# MergenElektronik_DesignBlocks_USB_Type-C.net
KiCad netlist of a schematic drawn in Altium Designer
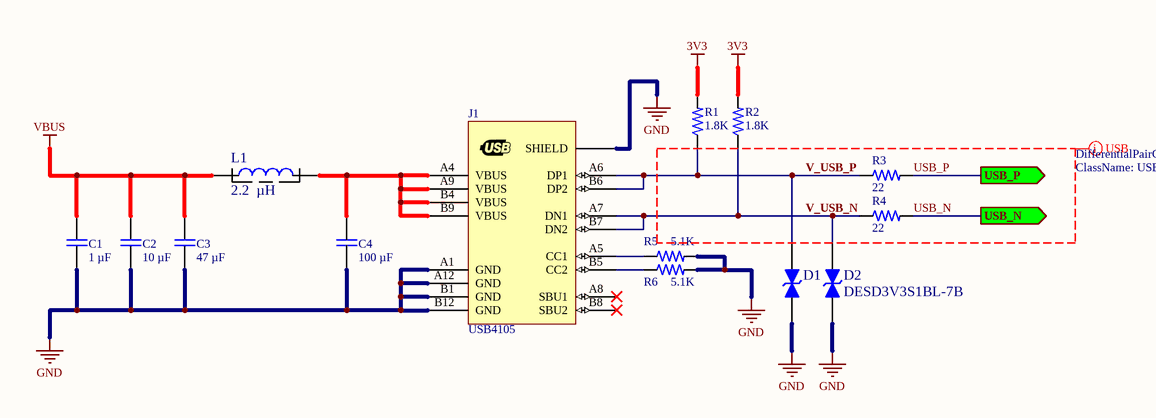
[diagram p0: MergenElektronik_DesignBlocks_USB_Type-C-Device.SchDoc]

(export (version "E")
  (design (tool "Eeschema 10.0.6"))
  (components
    (comp (ref "C1")
      (value "1 µF")
      (footprint "MergenElektronik_Capacitors_Ceramics_SMDs_1206_S_NS")
      (description "Mergen Elektronik - Capacitors - Ceramics - SMDs - 1206 - 1 µF - 100V")
      (fields (field (name "MANUFACTURER") "Samsung Electro-Mechanics") (field (name "TOLERANCE") "±10%"))
      (libsource (lib "MergenElektronik_Capacitors_Ceramics_SMDs") (part "MergenElektronik_Capacitors_Ceramic_SMDs_1µF_100V"))
    )
    (comp (ref "C2")
      (value "10 µF")
      (footprint "MergenElektronik_Capacitors_Ceramics_SMDs_0603_S_NS")
      (description "Mergen Elektronik - Capacitors - Ceramics - SMDs - 0603 - 10 µF - 25V")
      (fields (field (name "MANUFACTURER") "Murata Electronics") (field (name "TOLERANCE") "±20%"))
      (libsource (lib "MergenElektronik_Capacitors_Ceramics_SMDs") (part "MergenElektronik_Capacitors_Ceramic_SMDs_10µF_25V"))
    )
    (comp (ref "C3")
      (value "47 µF")
      (footprint "MergenElektronik_Capacitors_Ceramics_SMDs_1206_L")
      (description "Mergen Elektronik - Capacitors - Ceramics - SMDs - 1206 - 47 µF - 25V")
      (fields (field (name "MANUFACTURER") "TDK Corporation") (field (name "TOLERANCE") "±20%"))
      (libsource (lib "MergenElektronik_Capacitors_Ceramics_SMDs") (part "MergenElektronik_Capacitors_Ceramic_SMDs_47µF_25V"))
    )
    (comp (ref "C4")
      (value "100 µF")
      (footprint "MergenElektronik_Capacitors_Ceramics_SMDs_1210_S_NS")
      (description "Mergen Elektronik - Capacitors - Ceramics - SMDs - 1210 - 100 µF - 10V")
      (fields (field (name "MANUFACTURER") "Samsung Electro-Mechanics") (field (name "TOLERANCE") "±20%"))
      (libsource (lib "MergenElektronik_Capacitors_Ceramics_SMDs") (part "MergenElektronik_Capacitors_Ceramic_SMDs_100µF_10V"))
    )
    (comp (ref "D1")
      (value "DESD3V3S1BL-7B")
      (footprint "MergenElektronik_Diodes_TVSDiodes_0402_L")
      (description "Mergen Elektronik - Diodes - TVS Diodes - DESD3V3S1BL-7B")
      (fields (field (name "MANUFACTURER") "Diodes Incorporated"))
      (libsource (lib "MergenElektronik_Diodes_TVSDiodes") (part "MergenElektronik_Diodes_TVSDiodes_DESD3V3S1BL-7B"))
    )
    (comp (ref "D2")
      (value "DESD3V3S1BL-7B")
      (footprint "MergenElektronik_Diodes_TVSDiodes_0402_L")
      (description "Mergen Elektronik - Diodes - TVS Diodes - DESD3V3S1BL-7B")
      (fields (field (name "MANUFACTURER") "Diodes Incorporated"))
      (libsource (lib "MergenElektronik_Diodes_TVSDiodes") (part "MergenElektronik_Diodes_TVSDiodes_DESD3V3S1BL-7B"))
    )
    (comp (ref "J1")
      (value "USB4105")
      (footprint "MergenElektronik_Connectors_USB_USB4105")
      (description "Mergen Elektronik - Connectors - USB Connectors - USB4105")
      (fields (field (name "MANUFACTURER") "GCT"))
      (libsource (lib "MergenElektronik_Connectors_USB") (part "MergenElektronik_Connectors_USB_USB4105"))
    )
    (comp (ref "L1")
      (value "2.2  µH")
      (footprint "MergenElektronik_Inductors_PowerInductors_SMDs_1008_S_NS")
      (description "Mergen Elektronik - Inductors - Power Inductors - SMDs - 1008 - 2.2 µh - 2A")
      (fields (field (name "MANUFACTURER") "Samsung Electro-Mechanics"))
      (libsource (lib "MergenElektronik_Inductors_PowerInductors_SMDs") (part "MergenElektronik_Inductors_PowerInductors_SMDs_1008_2.2µH-2A"))
    )
    (comp (ref "R1")
      (value "1.8K")
      (footprint "MergenElektronik_Resistors_ChipResistors_0603_S_NS")
      (description "Mergen Elektronik - Resistors - Chip Resistors - 0603 - 1.8K")
      (fields (field (name "MANUFACTURER") "Stackpole Electronics Inc") (field (name "POWER") "1/10W"))
      (libsource (lib "MergenElektronik_Resistors_ChipResistors") (part "MergenElektronik_Resistors_ChipResistors_0603_1.8K"))
    )
    (comp (ref "R2")
      (value "1.8K")
      (footprint "MergenElektronik_Resistors_ChipResistors_0603_S_NS")
      (description "Mergen Elektronik - Resistors - Chip Resistors - 0603 - 1.8K")
      (fields (field (name "MANUFACTURER") "Stackpole Electronics Inc") (field (name "POWER") "1/10W"))
      (libsource (lib "MergenElektronik_Resistors_ChipResistors") (part "MergenElektronik_Resistors_ChipResistors_0603_1.8K"))
    )
    (comp (ref "R3")
      (value "22")
      (footprint "MergenElektronik_Resistors_ChipResistors_0603_S")
      (description "Mergen Elektronik - Resistors - Chip Resistors - 0603 - 22")
      (fields (field (name "MANUFACTURER") "TE Connectivity Passive Product") (field (name "POWER") "1/10W"))
      (libsource (lib "MergenElektronik_Resistors_ChipResistors") (part "MergenElektronik_Resistors_ChipResistors_0603_22"))
    )
    (comp (ref "R4")
      (value "22")
      (footprint "MergenElektronik_Resistors_ChipResistors_0603_S")
      (description "Mergen Elektronik - Resistors - Chip Resistors - 0603 - 22")
      (fields (field (name "MANUFACTURER") "TE Connectivity Passive Product") (field (name "POWER") "1/10W"))
      (libsource (lib "MergenElektronik_Resistors_ChipResistors") (part "MergenElektronik_Resistors_ChipResistors_0603_22"))
    )
    (comp (ref "R5")
      (value "5.1K")
      (footprint "MergenElektronik_Resistors_ChipResistors_0603_S_NS")
      (description "Mergen Elektronik - Resistors - Chip Resistors - 0603 - 5.1K")
      (fields (field (name "MANUFACTURER") "Stackpole Electronics Inc") (field (name "POWER") "1/10W"))
      (libsource (lib "MergenElektronik_Resistors_ChipResistors") (part "MergenElektronik_Resistors_ChipResistors_0603_5.1K"))
    )
    (comp (ref "R6")
      (value "5.1K")
      (footprint "MergenElektronik_Resistors_ChipResistors_0603_S_NS")
      (description "Mergen Elektronik - Resistors - Chip Resistors - 0603 - 5.1K")
      (fields (field (name "MANUFACTURER") "Stackpole Electronics Inc") (field (name "POWER") "1/10W"))
      (libsource (lib "MergenElektronik_Resistors_ChipResistors") (part "MergenElektronik_Resistors_ChipResistors_0603_5.1K"))
    )
  )
  (nets
    (net (code "1") (name "/USB_N") (class "Default")
      (node (ref "R4") (pin "2") (pinfunction "2_2") (pintype "passive"))
    )
    (net (code "2") (name "/USB_P") (class "Default")
      (node (ref "R3") (pin "2") (pinfunction "2_2") (pintype "passive"))
    )
    (net (code "3") (name "/V_USB_N") (class "Default")
      (node (ref "D2") (pin "2") (pinfunction "KATOT_2") (pintype "passive"))
      (node (ref "J1") (pin "A7") (pinfunction "DN1_A7") (pintype "bidirectional"))
      (node (ref "J1") (pin "B7") (pinfunction "DN2_B7") (pintype "bidirectional"))
      (node (ref "R2") (pin "1") (pinfunction "1_1") (pintype "passive"))
      (node (ref "R4") (pin "1") (pinfunction "1_1") (pintype "passive"))
    )
    (net (code "4") (name "/V_USB_P") (class "Default")
      (node (ref "D1") (pin "2") (pinfunction "KATOT_2") (pintype "passive"))
      (node (ref "J1") (pin "A6") (pinfunction "DP1_A6") (pintype "bidirectional"))
      (node (ref "J1") (pin "B6") (pinfunction "DP2_B6") (pintype "bidirectional"))
      (node (ref "R1") (pin "1") (pinfunction "1_1") (pintype "passive"))
      (node (ref "R3") (pin "1") (pinfunction "1_1") (pintype "passive"))
    )
    (net (code "5") (name "3V3") (class "Default")
      (node (ref "R1") (pin "2") (pinfunction "2_2") (pintype "passive"))
      (node (ref "R2") (pin "2") (pinfunction "2_2") (pintype "passive"))
    )
    (net (code "6") (name "GND") (class "Default")
      (node (ref "C1") (pin "2") (pinfunction "2_2") (pintype "passive"))
      (node (ref "C2") (pin "2") (pinfunction "2_2") (pintype "passive"))
      (node (ref "C3") (pin "2") (pinfunction "2_2") (pintype "passive"))
      (node (ref "C4") (pin "2") (pinfunction "2_2") (pintype "passive"))
      (node (ref "D1") (pin "1") (pinfunction "ANOT_1") (pintype "passive"))
      (node (ref "D2") (pin "1") (pinfunction "ANOT_1") (pintype "passive"))
      (node (ref "J1") (pin "A1") (pinfunction "GND_A1") (pintype "power_in"))
      (node (ref "J1") (pin "A12") (pinfunction "GND_A12") (pintype "power_in"))
      (node (ref "J1") (pin "B1") (pinfunction "GND_B1") (pintype "power_in"))
      (node (ref "J1") (pin "B12") (pinfunction "GND_B12") (pintype "power_in"))
      (node (ref "J1") (pin "SHIELD") (pinfunction "SHIELD_SHIELD") (pintype "power_in"))
      (node (ref "R5") (pin "2") (pinfunction "2_2") (pintype "passive"))
      (node (ref "R6") (pin "2") (pinfunction "2_2") (pintype "passive"))
    )
    (net (code "7") (name "Net-(C4-Pad1)") (class "Default")
      (node (ref "C4") (pin "1") (pinfunction "1_1") (pintype "passive"))
      (node (ref "J1") (pin "A4") (pinfunction "VBUS_A4") (pintype "power_in"))
      (node (ref "J1") (pin "A9") (pinfunction "VBUS_A9") (pintype "passive"))
      (node (ref "J1") (pin "B4") (pinfunction "VBUS_B4") (pintype "power_in"))
      (node (ref "J1") (pin "B9") (pinfunction "VBUS_B9") (pintype "power_in"))
      (node (ref "L1") (pin "2") (pinfunction "2_2") (pintype "passive"))
    )
    (net (code "8") (name "Net-(J1-CC1)") (class "Default")
      (node (ref "J1") (pin "A5") (pinfunction "CC1_A5") (pintype "bidirectional"))
      (node (ref "R5") (pin "1") (pinfunction "1_1") (pintype "passive"))
    )
    (net (code "9") (name "Net-(J1-CC2)") (class "Default")
      (node (ref "J1") (pin "B5") (pinfunction "CC2_B5") (pintype "bidirectional"))
      (node (ref "R6") (pin "1") (pinfunction "1_1") (pintype "passive"))
    )
    (net (code "10") (name "VBUS") (class "Default")
      (node (ref "C1") (pin "1") (pinfunction "1_1") (pintype "passive"))
      (node (ref "C2") (pin "1") (pinfunction "1_1") (pintype "passive"))
      (node (ref "C3") (pin "1") (pinfunction "1_1") (pintype "passive"))
      (node (ref "L1") (pin "1") (pinfunction "1_1") (pintype "passive"))
    )
    (net (code "11") (name "unconnected-(J1-SBU1-PadA8)") (class "Default")
      (node (ref "J1") (pin "A8") (pinfunction "SBU1_A8") (pintype "bidirectional+no_connect"))
    )
    (net (code "12") (name "unconnected-(J1-SBU2-PadB8)") (class "Default")
      (node (ref "J1") (pin "B8") (pinfunction "SBU2_B8") (pintype "bidirectional+no_connect"))
    )
  )
)
